# CAN_Sniffer_HAT.net
KiCad netlist of a schematic drawn in Altium Designer
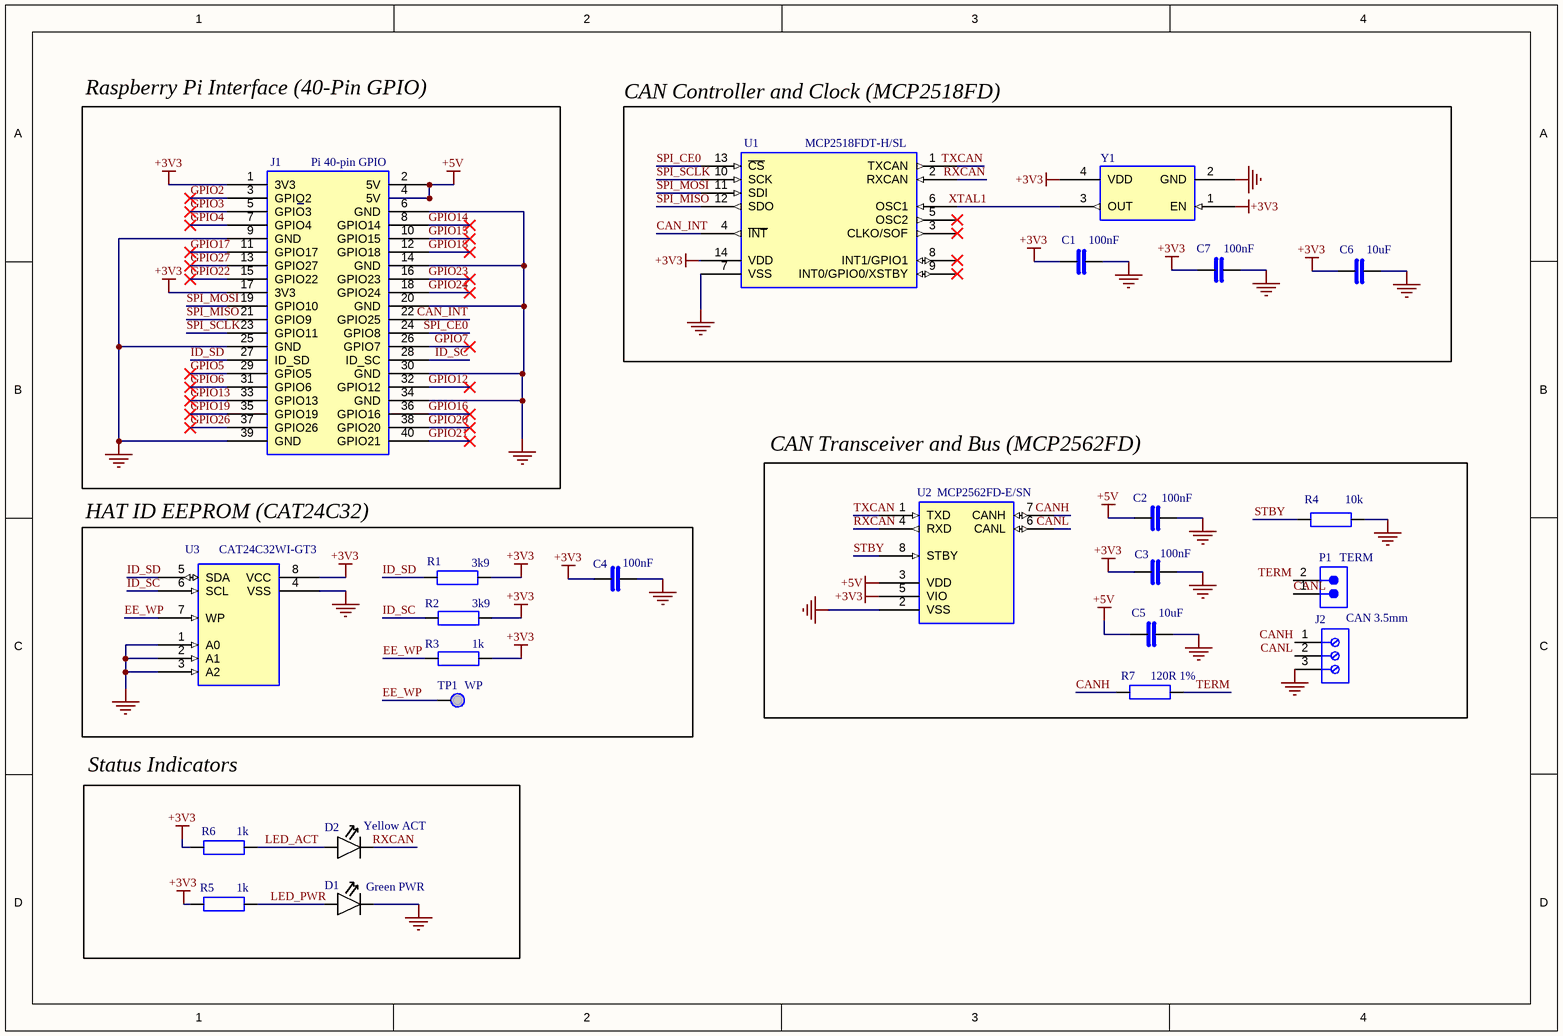
[diagram p0: CAN_Sniffer_HAT.SchDoc]

(export (version "E")
  (design (tool "Eeschema 10.0.6"))
  (components
    (comp (ref "C1")
      (value "100nF")
      (footprint "0805")
      (description "Capacitor, non-polarised, 0805")
      (libsource (lib "CAN_Sniffer_HAT") (part "CAP"))
    )
    (comp (ref "C2")
      (value "100nF")
      (footprint "0805")
      (description "Capacitor, non-polarised, 0805")
      (libsource (lib "CAN_Sniffer_HAT") (part "CAP"))
    )
    (comp (ref "C3")
      (value "100nF")
      (footprint "0805")
      (description "Capacitor, non-polarised, 0805")
      (libsource (lib "CAN_Sniffer_HAT") (part "CAP"))
    )
    (comp (ref "C4")
      (value "100nF")
      (footprint "0805")
      (description "Capacitor, non-polarised, 0805")
      (libsource (lib "CAN_Sniffer_HAT") (part "CAP"))
    )
    (comp (ref "C5")
      (value "10uF")
      (footprint "0805")
      (description "Capacitor, non-polarised, 0805")
      (libsource (lib "CAN_Sniffer_HAT") (part "CAP"))
    )
    (comp (ref "C6")
      (value "10uF")
      (footprint "0805")
      (description "Capacitor, non-polarised, 0805")
      (libsource (lib "CAN_Sniffer_HAT") (part "CAP"))
    )
    (comp (ref "C7")
      (value "100nF")
      (footprint "0805")
      (description "Capacitor, non-polarised, 0805")
      (libsource (lib "CAN_Sniffer_HAT") (part "CAP"))
    )
    (comp (ref "D1")
      (value "Green PWR")
      (footprint "LED_0805")
      (description "LED, 0805")
      (libsource (lib "CAN_Sniffer_HAT") (part "LED"))
    )
    (comp (ref "D2")
      (value "Yellow ACT")
      (footprint "LED_0805")
      (description "LED, 0805")
      (libsource (lib "CAN_Sniffer_HAT") (part "LED"))
    )
    (comp (ref "J1")
      (value "Pi 40-pin GPIO")
      (footprint "HDR_2X20_254")
      (description "Raspberry Pi 40-pin GPIO header, 2x20, 2.54 mm")
      (libsource (lib "CAN_Sniffer_HAT") (part "HDR_2X20_PI"))
    )
    (comp (ref "J2")
      (value "CAN 3.5mm")
      (footprint "691214110003")
      (description "2141 Series 3.5MM Pitch Straight, Pcb Terminal Block, Through Hole, 3 Way")
      (fields (field (name "VOLTAGE") "300V"))
      (libsource (lib "Altium Content Vault") (part "TBL - 1R - 03P - Screw"))
    )
    (comp (ref "P1")
      (value "TERM")
      (footprint "SMTC-TSW-102-26-XX-S")
      (description "0.025\" SQ Post Header, Through-hole, Vertical, -55 to 125 degC, 2.54 mm Pitch, 2-Pin, Male, RoHS")
      (fields (field (name "MANUFACTURER") "Samtec") (field (name "PARTNUMBER") "TSW-102-26-L-S"))
      (libsource (lib "Altium Content Vault") (part "SMTC-TSW-102-X-X-S-X"))
    )
    (comp (ref "R1")
      (value "3k9")
      (footprint "0805")
      (description "Resistor, 0805")
      (libsource (lib "CAN_Sniffer_HAT") (part "RES"))
    )
    (comp (ref "R2")
      (value "3k9")
      (footprint "0805")
      (description "Resistor, 0805")
      (libsource (lib "CAN_Sniffer_HAT") (part "RES"))
    )
    (comp (ref "R3")
      (value "1k")
      (footprint "0805")
      (description "Resistor, 0805")
      (libsource (lib "CAN_Sniffer_HAT") (part "RES"))
    )
    (comp (ref "R4")
      (value "10k")
      (footprint "0805")
      (description "Resistor, 0805")
      (libsource (lib "CAN_Sniffer_HAT") (part "RES"))
    )
    (comp (ref "R5")
      (value "1k")
      (footprint "0805")
      (description "Resistor, 0805")
      (libsource (lib "CAN_Sniffer_HAT") (part "RES"))
    )
    (comp (ref "R6")
      (value "1k")
      (footprint "0805")
      (description "Resistor, 0805")
      (libsource (lib "CAN_Sniffer_HAT") (part "RES"))
    )
    (comp (ref "R7")
      (value "120R 1%")
      (footprint "0805")
      (description "Resistor, 0805")
      (libsource (lib "CAN_Sniffer_HAT") (part "RES"))
    )
    (comp (ref "TP1")
      (value "WP")
      (footprint "TESTPOINT_60")
      (description "Test point / probe pad")
      (libsource (lib "CAN_Sniffer_HAT") (part "TESTPOINT"))
    )
    (comp (ref "U1")
      (value "MCP2518FDT-H/SL")
      (footprint "SOIC-14_150MIL")
      (description "CAN FD controller, SPI, 8 Mbit/s, SOIC-14")
      (libsource (lib "CAN_Sniffer_HAT") (part "MCP2518FD"))
    )
    (comp (ref "U2")
      (value "MCP2562FD-E/SN")
      (footprint "SOIC-8_150MIL")
      (description "CAN FD transceiver with VIO level shift, SOIC-8")
      (libsource (lib "CAN_Sniffer_HAT") (part "MCP2562FD"))
    )
    (comp (ref "U3")
      (value "CAT24C32WI-GT3")
      (footprint "SOIC-8_150MIL")
      (description "32 kbit I2C EEPROM, 16-bit addressing, HAT ID EEPROM, SOIC-8")
      (libsource (lib "CAN_Sniffer_HAT") (part "CAT24C32"))
    )
    (comp (ref "Y1")
      (value "OSCILLATOR")
      (footprint "XTAL_3225_4P")
      (libsource (lib "CAN_Sniffer_HAT") (part "OSCILLATOR"))
    )
  )
  (nets
    (net (code "1") (name "+3V3") (class "Default")
      (node (ref "C1") (pin "1") (pinfunction "1_1") (pintype "passive"))
      (node (ref "C3") (pin "1") (pinfunction "1_1") (pintype "passive"))
      (node (ref "C4") (pin "1") (pinfunction "1_1") (pintype "passive"))
      (node (ref "C6") (pin "1") (pinfunction "1_1") (pintype "passive"))
      (node (ref "C7") (pin "1") (pinfunction "1_1") (pintype "passive"))
      (node (ref "J1") (pin "1") (pinfunction "3V3_1") (pintype "passive"))
      (node (ref "J1") (pin "17") (pinfunction "3V3_17") (pintype "passive"))
      (node (ref "R1") (pin "2") (pinfunction "2_2") (pintype "passive"))
      (node (ref "R2") (pin "2") (pinfunction "2_2") (pintype "passive"))
      (node (ref "R3") (pin "2") (pinfunction "2_2") (pintype "passive"))
      (node (ref "R5") (pin "1") (pinfunction "1_1") (pintype "passive"))
      (node (ref "R6") (pin "1") (pinfunction "1_1") (pintype "passive"))
      (node (ref "U1") (pin "14") (pinfunction "VDD_14") (pintype "power_in"))
      (node (ref "U2") (pin "5") (pinfunction "VIO_5") (pintype "power_in"))
      (node (ref "U3") (pin "8") (pinfunction "VCC_8") (pintype "power_in"))
      (node (ref "Y1") (pin "1") (pinfunction "EN_1") (pintype "input"))
      (node (ref "Y1") (pin "4") (pinfunction "VDD_4") (pintype "power_in"))
    )
    (net (code "2") (name "+5V") (class "Default")
      (node (ref "C2") (pin "1") (pinfunction "1_1") (pintype "passive"))
      (node (ref "C5") (pin "1") (pinfunction "1_1") (pintype "passive"))
      (node (ref "J1") (pin "2") (pinfunction "5V_2") (pintype "passive"))
      (node (ref "J1") (pin "4") (pinfunction "5V_4") (pintype "passive"))
      (node (ref "U2") (pin "3") (pinfunction "VDD_3") (pintype "power_in"))
    )
    (net (code "3") (name "/CANH") (class "Default")
      (node (ref "J2") (pin "1") (pinfunction "1_1") (pintype "passive"))
      (node (ref "R7") (pin "1") (pinfunction "1_1") (pintype "passive"))
      (node (ref "U2") (pin "7") (pinfunction "CANH_7") (pintype "bidirectional"))
    )
    (net (code "4") (name "/CANL") (class "Default")
      (node (ref "J2") (pin "2") (pinfunction "2_2") (pintype "passive"))
      (node (ref "P1") (pin "1") (pinfunction "1_1") (pintype "passive"))
      (node (ref "U2") (pin "6") (pinfunction "CANL_6") (pintype "bidirectional"))
    )
    (net (code "5") (name "/CAN_INT") (class "Default")
      (node (ref "J1") (pin "22") (pinfunction "GPIO25_22") (pintype "passive"))
      (node (ref "U1") (pin "4") (pinfunction "~{INT}_4") (pintype "output"))
    )
    (net (code "6") (name "/EE_WP") (class "Default")
      (node (ref "R3") (pin "1") (pinfunction "1_1") (pintype "passive"))
      (node (ref "TP1") (pin "1") (pinfunction "TP_1") (pintype "passive"))
      (node (ref "U3") (pin "7") (pinfunction "WP_7") (pintype "input"))
    )
    (net (code "7") (name "/GPIO2") (class "Default")
      (node (ref "J1") (pin "3") (pinfunction "GPIO2_3") (pintype "passive+no_connect"))
    )
    (net (code "8") (name "/GPIO3") (class "Default")
      (node (ref "J1") (pin "5") (pinfunction "GPIO3_5") (pintype "passive+no_connect"))
    )
    (net (code "9") (name "/GPIO4") (class "Default")
      (node (ref "J1") (pin "7") (pinfunction "GPIO4_7") (pintype "passive+no_connect"))
    )
    (net (code "10") (name "/GPIO5") (class "Default")
      (node (ref "J1") (pin "29") (pinfunction "GPIO5_29") (pintype "passive+no_connect"))
    )
    (net (code "11") (name "/GPIO6") (class "Default")
      (node (ref "J1") (pin "31") (pinfunction "GPIO6_31") (pintype "passive+no_connect"))
    )
    (net (code "12") (name "/GPIO7") (class "Default")
      (node (ref "J1") (pin "26") (pinfunction "GPIO7_26") (pintype "passive+no_connect"))
    )
    (net (code "13") (name "/GPIO12") (class "Default")
      (node (ref "J1") (pin "32") (pinfunction "GPIO12_32") (pintype "passive+no_connect"))
    )
    (net (code "14") (name "/GPIO13") (class "Default")
      (node (ref "J1") (pin "33") (pinfunction "GPIO13_33") (pintype "passive+no_connect"))
    )
    (net (code "15") (name "/GPIO14") (class "Default")
      (node (ref "J1") (pin "8") (pinfunction "GPIO14_8") (pintype "passive+no_connect"))
    )
    (net (code "16") (name "/GPIO15") (class "Default")
      (node (ref "J1") (pin "10") (pinfunction "GPIO15_10") (pintype "passive+no_connect"))
    )
    (net (code "17") (name "/GPIO16") (class "Default")
      (node (ref "J1") (pin "36") (pinfunction "GPIO16_36") (pintype "passive+no_connect"))
    )
    (net (code "18") (name "/GPIO17") (class "Default")
      (node (ref "J1") (pin "11") (pinfunction "GPIO17_11") (pintype "passive+no_connect"))
    )
    (net (code "19") (name "/GPIO18") (class "Default")
      (node (ref "J1") (pin "12") (pinfunction "GPIO18_12") (pintype "passive+no_connect"))
    )
    (net (code "20") (name "/GPIO19") (class "Default")
      (node (ref "J1") (pin "35") (pinfunction "GPIO19_35") (pintype "passive+no_connect"))
    )
    (net (code "21") (name "/GPIO20") (class "Default")
      (node (ref "J1") (pin "38") (pinfunction "GPIO20_38") (pintype "passive+no_connect"))
    )
    (net (code "22") (name "/GPIO21") (class "Default")
      (node (ref "J1") (pin "40") (pinfunction "GPIO21_40") (pintype "passive+no_connect"))
    )
    (net (code "23") (name "/GPIO22") (class "Default")
      (node (ref "J1") (pin "15") (pinfunction "GPIO22_15") (pintype "passive+no_connect"))
    )
    (net (code "24") (name "/GPIO23") (class "Default")
      (node (ref "J1") (pin "16") (pinfunction "GPIO23_16") (pintype "passive+no_connect"))
    )
    (net (code "25") (name "/GPIO24") (class "Default")
      (node (ref "J1") (pin "18") (pinfunction "GPIO24_18") (pintype "passive+no_connect"))
    )
    (net (code "26") (name "/GPIO26") (class "Default")
      (node (ref "J1") (pin "37") (pinfunction "GPIO26_37") (pintype "passive+no_connect"))
    )
    (net (code "27") (name "/GPIO27") (class "Default")
      (node (ref "J1") (pin "13") (pinfunction "GPIO27_13") (pintype "passive+no_connect"))
    )
    (net (code "28") (name "/ID_SC") (class "Default")
      (node (ref "J1") (pin "28") (pinfunction "ID_SC_28") (pintype "passive"))
      (node (ref "R2") (pin "1") (pinfunction "1_1") (pintype "passive"))
      (node (ref "U3") (pin "6") (pinfunction "SCL_6") (pintype "input"))
    )
    (net (code "29") (name "/ID_SD") (class "Default")
      (node (ref "J1") (pin "27") (pinfunction "ID_SD_27") (pintype "passive"))
      (node (ref "R1") (pin "1") (pinfunction "1_1") (pintype "passive"))
      (node (ref "U3") (pin "5") (pinfunction "SDA_5") (pintype "bidirectional"))
    )
    (net (code "30") (name "/LED_ACT") (class "Default")
      (node (ref "D2") (pin "1") (pinfunction "A_1") (pintype "passive"))
      (node (ref "R6") (pin "2") (pinfunction "2_2") (pintype "passive"))
    )
    (net (code "31") (name "/LED_PWR") (class "Default")
      (node (ref "D1") (pin "1") (pinfunction "A_1") (pintype "passive"))
      (node (ref "R5") (pin "2") (pinfunction "2_2") (pintype "passive"))
    )
    (net (code "32") (name "/RXCAN") (class "Default")
      (node (ref "D2") (pin "2") (pinfunction "K_2") (pintype "passive"))
      (node (ref "U1") (pin "2") (pinfunction "RXCAN_2") (pintype "input"))
      (node (ref "U2") (pin "4") (pinfunction "RXD_4") (pintype "output"))
    )
    (net (code "33") (name "/SPI_CE0") (class "Default")
      (node (ref "J1") (pin "24") (pinfunction "GPIO8_24") (pintype "passive"))
      (node (ref "U1") (pin "13") (pinfunction "~{CS}_13") (pintype "input"))
    )
    (net (code "34") (name "/SPI_MISO") (class "Default")
      (node (ref "J1") (pin "21") (pinfunction "GPIO9_21") (pintype "passive"))
      (node (ref "U1") (pin "12") (pinfunction "SDO_12") (pintype "output"))
    )
    (net (code "35") (name "/SPI_MOSI") (class "Default")
      (node (ref "J1") (pin "19") (pinfunction "GPIO10_19") (pintype "passive"))
      (node (ref "U1") (pin "11") (pinfunction "SDI_11") (pintype "input"))
    )
    (net (code "36") (name "/SPI_SCLK") (class "Default")
      (node (ref "J1") (pin "23") (pinfunction "GPIO11_23") (pintype "passive"))
      (node (ref "U1") (pin "10") (pinfunction "SCK_10") (pintype "input"))
    )
    (net (code "37") (name "/STBY") (class "Default")
      (node (ref "R4") (pin "1") (pinfunction "1_1") (pintype "passive"))
      (node (ref "U2") (pin "8") (pinfunction "STBY_8") (pintype "input"))
    )
    (net (code "38") (name "/TERM") (class "Default")
      (node (ref "P1") (pin "2") (pinfunction "2_2") (pintype "passive"))
      (node (ref "R7") (pin "2") (pinfunction "2_2") (pintype "passive"))
    )
    (net (code "39") (name "/TXCAN") (class "Default")
      (node (ref "U1") (pin "1") (pinfunction "TXCAN_1") (pintype "output"))
      (node (ref "U2") (pin "1") (pinfunction "TXD_1") (pintype "input"))
    )
    (net (code "40") (name "/XTAL1") (class "Default")
      (node (ref "U1") (pin "6") (pinfunction "OSC1_6") (pintype "input"))
      (node (ref "Y1") (pin "3") (pinfunction "OUT_3") (pintype "output"))
    )
    (net (code "41") (name "GND") (class "Default")
      (node (ref "C1") (pin "2") (pinfunction "2_2") (pintype "passive"))
      (node (ref "C2") (pin "2") (pinfunction "2_2") (pintype "passive"))
      (node (ref "C3") (pin "2") (pinfunction "2_2") (pintype "passive"))
      (node (ref "C4") (pin "2") (pinfunction "2_2") (pintype "passive"))
      (node (ref "C5") (pin "2") (pinfunction "2_2") (pintype "passive"))
      (node (ref "C6") (pin "2") (pinfunction "2_2") (pintype "passive"))
      (node (ref "C7") (pin "2") (pinfunction "2_2") (pintype "passive"))
      (node (ref "D1") (pin "2") (pinfunction "K_2") (pintype "passive"))
      (node (ref "J1") (pin "14") (pinfunction "GND_14") (pintype "passive"))
      (node (ref "J1") (pin "20") (pinfunction "GND_20") (pintype "passive"))
      (node (ref "J1") (pin "25") (pinfunction "GND_25") (pintype "passive"))
      (node (ref "J1") (pin "30") (pinfunction "GND_30") (pintype "passive"))
      (node (ref "J1") (pin "34") (pinfunction "GND_34") (pintype "passive"))
      (node (ref "J1") (pin "39") (pinfunction "GND_39") (pintype "passive"))
      (node (ref "J1") (pin "6") (pinfunction "GND_6") (pintype "passive"))
      (node (ref "J1") (pin "9") (pinfunction "GND_9") (pintype "passive"))
      (node (ref "J2") (pin "3") (pinfunction "3_3") (pintype "passive"))
      (node (ref "R4") (pin "2") (pinfunction "2_2") (pintype "passive"))
      (node (ref "U1") (pin "7") (pinfunction "VSS_7") (pintype "power_in"))
      (node (ref "U2") (pin "2") (pinfunction "VSS_2") (pintype "power_in"))
      (node (ref "U3") (pin "1") (pinfunction "A0_1") (pintype "input"))
      (node (ref "U3") (pin "2") (pinfunction "A1_2") (pintype "input"))
      (node (ref "U3") (pin "3") (pinfunction "A2_3") (pintype "input"))
      (node (ref "U3") (pin "4") (pinfunction "VSS_4") (pintype "power_in"))
      (node (ref "Y1") (pin "2") (pinfunction "GND_2") (pintype "passive"))
    )
    (net (code "42") (name "unconnected-(U1-CLKO{slash}SOF-Pad3)") (class "Default")
      (node (ref "U1") (pin "3") (pinfunction "CLKO/SOF_3") (pintype "output+no_connect"))
    )
    (net (code "43") (name "unconnected-(U1-INT0{slash}GPIO0{slash}XSTBY-Pad9)") (class "Default")
      (node (ref "U1") (pin "9") (pinfunction "INT0/GPIO0/XSTBY_9") (pintype "bidirectional+no_connect"))
    )
    (net (code "44") (name "unconnected-(U1-INT1{slash}GPIO1-Pad8)") (class "Default")
      (node (ref "U1") (pin "8") (pinfunction "INT1/GPIO1_8") (pintype "bidirectional+no_connect"))
    )
    (net (code "45") (name "unconnected-(U1-OSC2-Pad5)") (class "Default")
      (node (ref "U1") (pin "5") (pinfunction "OSC2_5") (pintype "output+no_connect"))
    )
  )
)
